# ESP32.net
KiCad netlist of a schematic drawn in Altium Designer
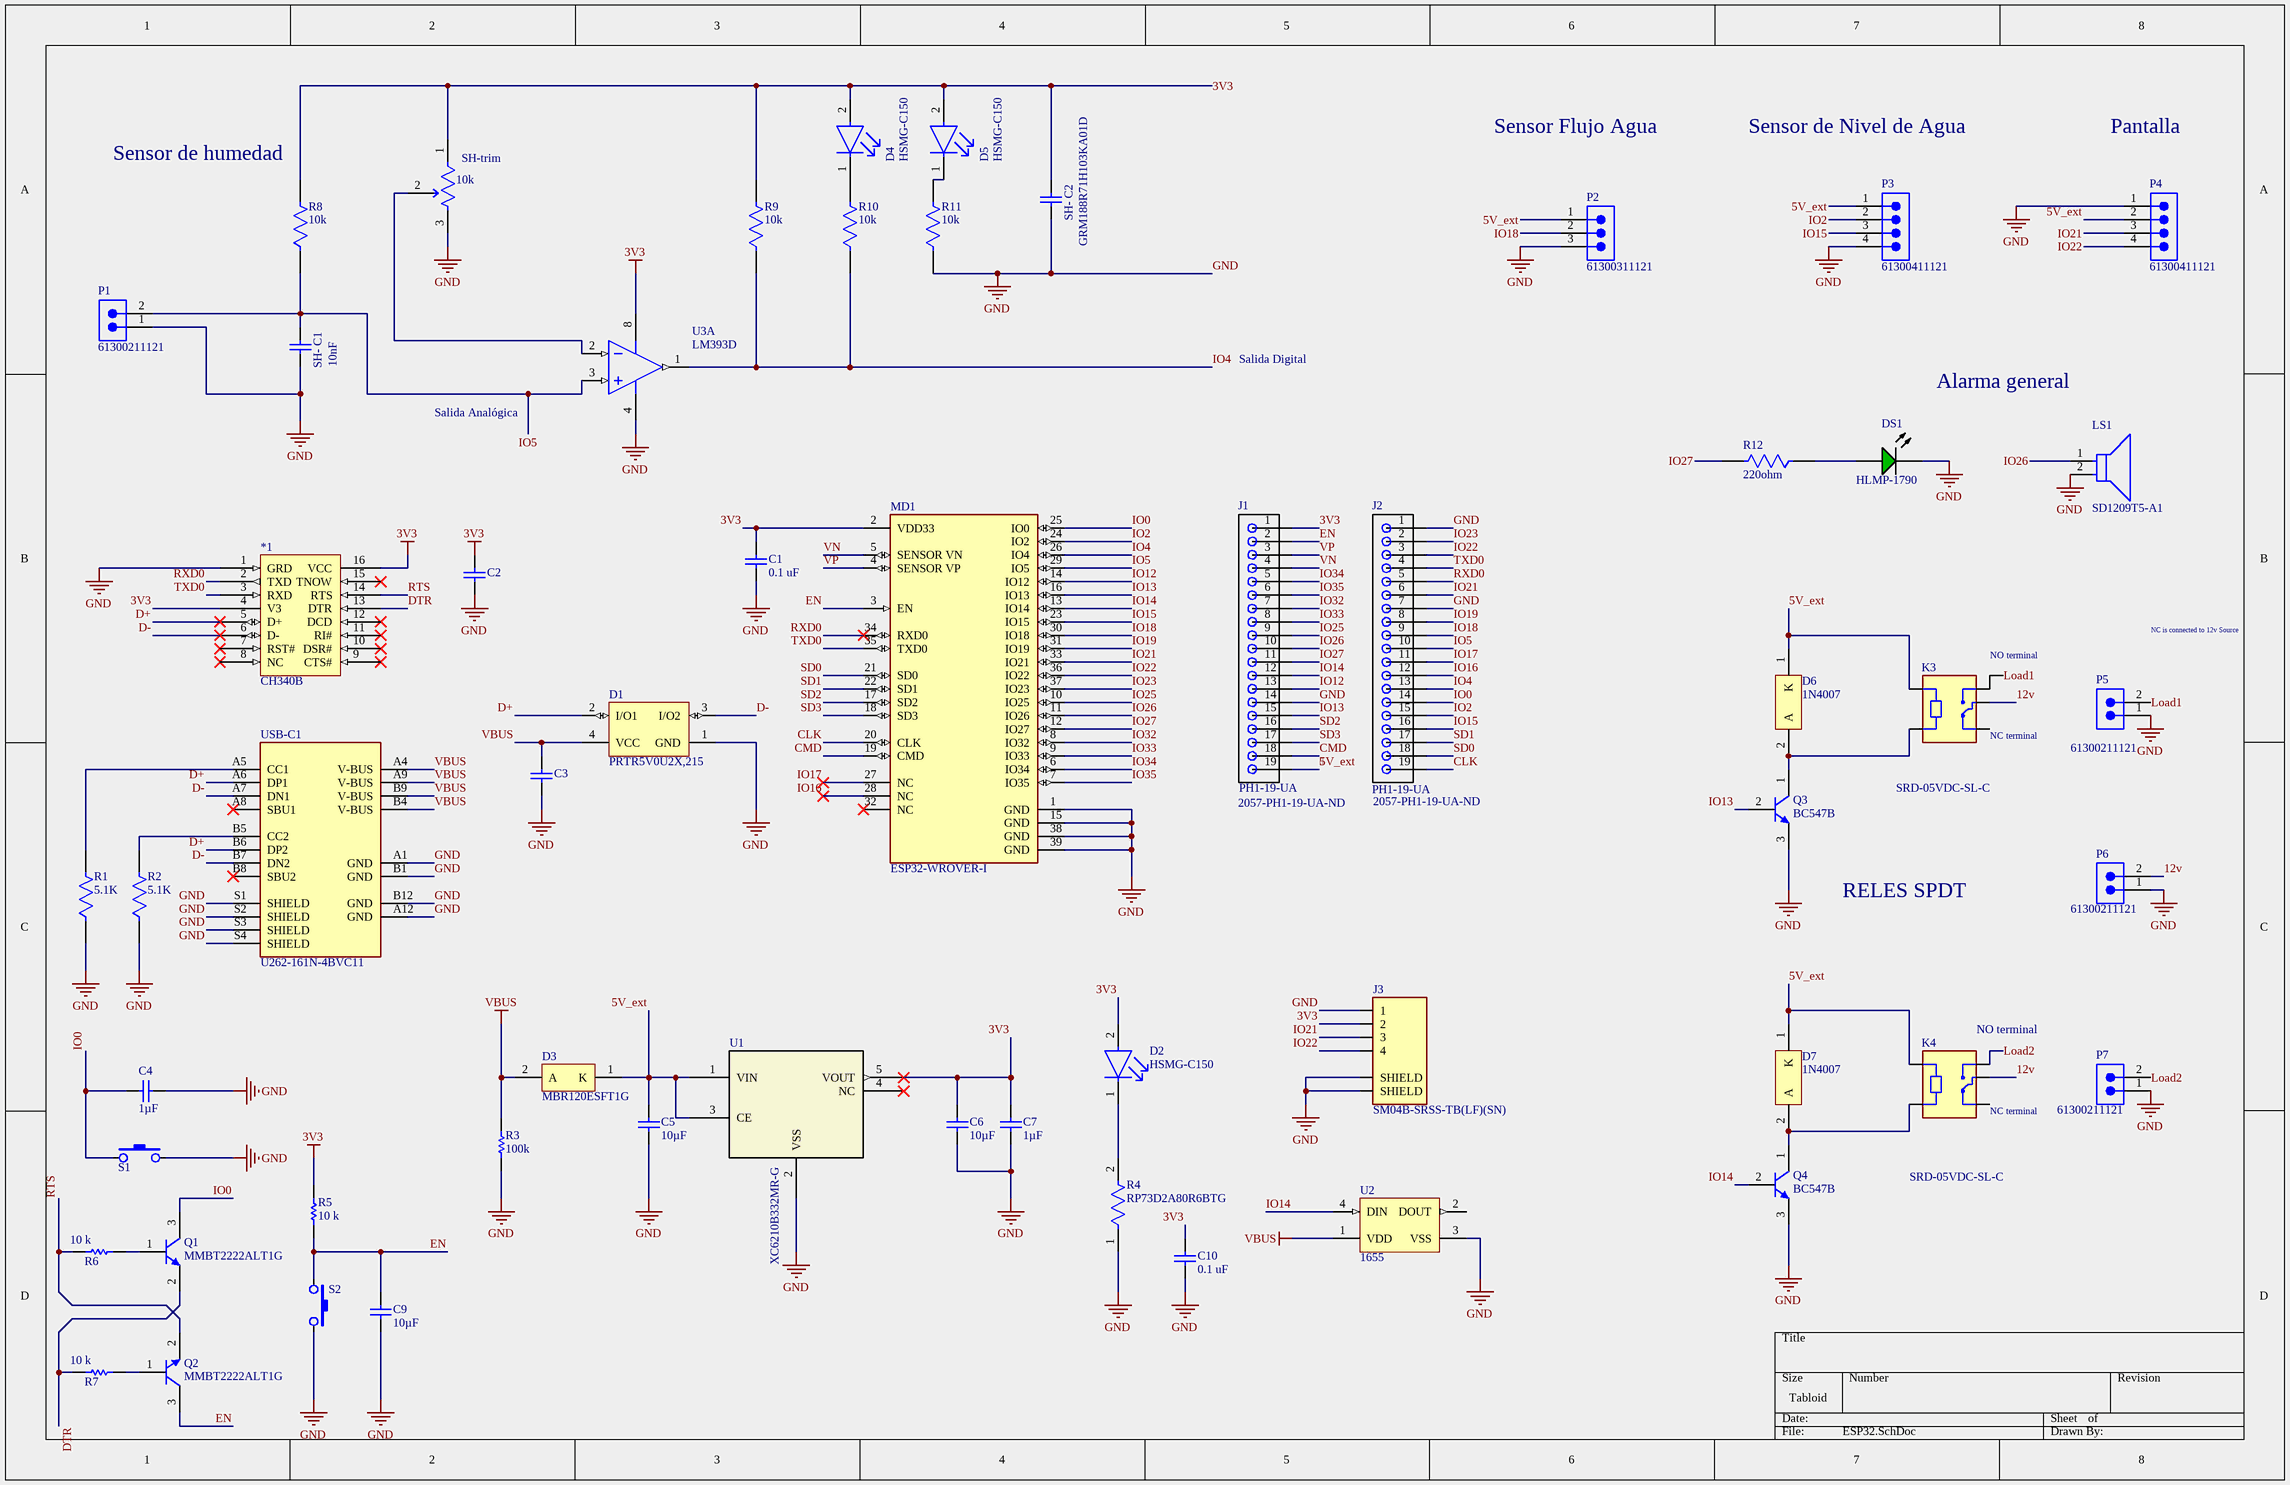
[diagram p0: ESP32.SchDoc]

(export (version "E")
  (design (tool "Eeschema 10.0.6"))
  (components
    (comp (ref "*1")
      (value "CH340B")
      (footprint "CH340B")
      (description "- USB 2.0 Transceiver 2Mbps SOP-16_150mil USB ICs ROHS")
      (libsource (lib "Isidro_Library") (part "CH340B"))
    )
    (comp (ref "C1")
      (value "0.1 uF")
      (footprint "CAPC2013X94X50ML20T25")
      (description "Chip Capacitor, Ceramic, 0.1 uF, 10%, 50 V, 0805, RoHS, Tape and Reel")
      (fields (field (name "MANUFACTURER") "AVX"))
      (libsource (lib "Altium Content Vault") (part "CAP-NP-2"))
    )
    (comp (ref "C2")
      (value "08055C104KAT2A")
      (footprint "CAPC2013X94X50ML20T25")
      (description "Chip Capacitor, Ceramic, 0.1 uF, 10%, 50 V, 0805, RoHS, Tape and Reel")
      (fields (field (name "MANUFACTURER") "AVX"))
      (libsource (lib "Altium Content Vault") (part "CAP-NP-2"))
    )
    (comp (ref "C3")
      (value "08055C104KAT2A")
      (footprint "CAPC2013X94X50ML20T25")
      (description "Chip Capacitor, Ceramic, 0.1 uF, 10%, 50 V, 0805, RoHS, Tape and Reel")
      (fields (field (name "MANUFACTURER") "AVX"))
      (libsource (lib "Altium Content Vault") (part "CAP-NP-2"))
    )
    (comp (ref "C4")
      (value "1µF")
      (footprint "CAPC2013X145X50ML20T25")
      (description "1µF ±10% 16V Ceramic Capacitor X7R 0805 (2012 Metric)")
      (fields (field (name "MANUFACTURER") "Kemet") (field (name "PART NUMBER") "C0805C105K4RAC7800"))
      (libsource (lib "Altium Content Vault") (part "CAP"))
    )
    (comp (ref "C5")
      (value "10µF")
      (footprint "CAPC2013X140X50ML20T25")
      (description "10µF ±10% 16V Ceramic Capacitor X5R 0805 (2012 Metric)")
      (fields (field (name "PART NUMBER") "CL21A106KOQNNNG"))
      (libsource (lib "Altium Content Vault") (part "CAP"))
    )
    (comp (ref "C6")
      (value "10µF")
      (footprint "CAPC2013X140X50ML20T25")
      (description "10µF ±10% 16V Ceramic Capacitor X5R 0805 (2012 Metric)")
      (fields (field (name "PART NUMBER") "CL21A106KOQNNNG"))
      (libsource (lib "Altium Content Vault") (part "CAP"))
    )
    (comp (ref "C7")
      (value "1µF")
      (footprint "CAPC2013X145X50ML20T25")
      (description "1µF ±10% 16V Ceramic Capacitor X7R 0805 (2012 Metric)")
      (fields (field (name "MANUFACTURER") "Kemet") (field (name "PART NUMBER") "C0805C105K4RAC7800"))
      (libsource (lib "Altium Content Vault") (part "CAP"))
    )
    (comp (ref "C9")
      (value "10µF")
      (footprint "CAPC2013X145X50ML20T25")
      (description "1µF ±10% 16V Ceramic Capacitor X7R 0805 (2012 Metric)")
      (fields (field (name "MANUFACTURER") "Kemet") (field (name "PART NUMBER") "C0805C105K4RAC7800"))
      (libsource (lib "Altium Content Vault") (part "CAP"))
    )
    (comp (ref "C10")
      (value "0.1 uF")
      (footprint "CAPC2013X94X50ML20T25")
      (description "Chip Capacitor, Ceramic, 0.1 uF, 10%, 50 V, 0805, RoHS, Tape and Reel")
      (fields (field (name "MANUFACTURER") "AVX"))
      (libsource (lib "Altium Content Vault") (part "CAP-NP-2"))
    )
    (comp (ref "D1")
      (value "PRTR5V0U2X,215")
      (footprint "NXP-SOT143B-4_V")
      (fields (field (name "MANUFACTURER") "NXP Semiconductors"))
      (libsource (lib "Altium Content Vault") (part "NXP-PRTR5V0U2X,215-4"))
    )
    (comp (ref "D2")
      (value "HSMG-C150")
      (footprint "FP-HSMG-C150-MFG")
      (description "LED GREEN DIFFUSED 1206 SMD")
      (fields
        (field (name "MANUFACTURER") "Broadcom")
        (field (name "OCTOPART") "https://octopart.com/hsmg-c150-broadcom-71131304")
      )
      (libsource (lib "Altium Content Vault") (part "8706943c75ba83719d021d2fdc84c58"))
    )
    (comp (ref "D3")
      (value "MBR120ESFT1G")
      (footprint "ONSC-SOD-123FL-2-498_V")
      (description "Schottky Power Rectifier, 2-Pin SOD-123, Pb-Free, Tape and Reel")
      (fields (field (name "MANUFACTURER") "On Semiconductor"))
      (libsource (lib "Altium Content Vault") (part "ONSC-D-K1A2-2_A"))
    )
    (comp (ref "D4")
      (value "HSMG-C150")
      (footprint "FP-HSMG-C150-MFG")
      (description "LED GREEN DIFFUSED 1206 SMD")
      (fields
        (field (name "MANUFACTURER") "Broadcom")
        (field (name "OCTOPART") "https://octopart.com/hsmg-c150-broadcom-71131304")
      )
      (libsource (lib "Altium Content Vault") (part "8706943c75ba83719d021d2fdc84c58"))
    )
    (comp (ref "D5")
      (value "HSMG-C150")
      (footprint "FP-HSMG-C150-MFG")
      (description "LED GREEN DIFFUSED 1206 SMD")
      (fields
        (field (name "MANUFACTURER") "Broadcom")
        (field (name "OCTOPART") "https://octopart.com/hsmg-c150-broadcom-71131304")
      )
      (libsource (lib "Altium Content Vault") (part "8706943c75ba83719d021d2fdc84c58"))
    )
    (comp (ref "D6")
      (value "1N4007")
      (footprint "ONSC-AXIAL_LEAD-2-59-10_P")
      (description "Standard Recovery Rectifier, 2-Pin Axial_Lead, Pb-Free, Bulk Bag")
      (fields (field (name "MANUFACTURER") "On Semiconductor"))
      (libsource (lib "") (part "ONSC-D-K1A2-2_A_1"))
    )
    (comp (ref "D7")
      (value "1N4007")
      (footprint "ONSC-AXIAL_LEAD-2-59-10_P")
      (description "Standard Recovery Rectifier, 2-Pin Axial_Lead, Pb-Free, Bulk Bag")
      (fields (field (name "MANUFACTURER") "On Semiconductor"))
      (libsource (lib "") (part "ONSC-D-K1A2-2_A_1"))
    )
    (comp (ref "DS1")
      (value "HLMP-1790")
      (footprint "LED-2P-2.54-3MM_V")
      (description "LED, Green, 2 mA, 1.9 V, -20 to 100 degC, 2-Pin THD, RoHS, Bulk")
      (fields (field (name "MANUFACTURER") "Avago"))
      (libsource (lib "Altium Content Vault") (part "LED_GREEN_A1K2-2"))
    )
    (comp (ref "J1")
      (value "PH1-19-UA")
      (footprint "PH1-19-UA")
      (description "Connector Header Through Hole 19 position 0.100\" (2.54mm)")
      (fields (field (name "SUPPLIER PART NUMBER 1") "2057-PH1-19-UA-ND"))
      (libsource (lib "Isidro_Library") (part "PH1-19-UA"))
    )
    (comp (ref "J2")
      (value "PH1-19-UA")
      (footprint "PH1-19-UA")
      (description "Connector Header Through Hole 19 position 0.100\" (2.54mm)")
      (fields (field (name "SUPPLIER PART NUMBER 1") "2057-PH1-19-UA-ND"))
      (libsource (lib "Isidro_Library") (part "PH1-19-UA"))
    )
    (comp (ref "J3")
      (value "SM04B-SRSS-TB(LF)(SN)")
      (footprint "JST_SM04B-SRSS-TB(LF)(SN)")
      (description "Connector Header Surface Mount, Right Angle 4 position 0.039 _1.00mm_")
      (fields (field (name "MF") "JST Sales") (field (name "MP") "SM04B-SRSS-TB_LF__SN_"))
      (libsource (lib "Isidro_Library") (part "SM04B-SRSS-TB(LF)(SN)"))
    )
    (comp (ref "K3")
      (value "SRD-05VDC-SL-C")
      (footprint "RELAY_SRD-05VDC-SL-C")
      (fields (field (name "MF") "Songle Relay"))
      (libsource (lib "SRD-05VDC-SL-C") (part "SRD-05VDC-SL-C"))
    )
    (comp (ref "K4")
      (value "SRD-05VDC-SL-C")
      (footprint "RELAY_SRD-05VDC-SL-C")
      (fields (field (name "MF") "Songle Relay"))
      (libsource (lib "SRD-05VDC-SL-C") (part "SRD-05VDC-SL-C"))
    )
    (comp (ref "LS1")
      (value "SD1209T5-A1")
      (footprint "FP-SD1209-MFG")
      (description "AUDIO MAGNETIC XDCR 3-6V TH")
      (libsource (lib "Altium Content Vault") (part "1973c4b650225fd2ddacaff6b763965"))
    )
    (comp (ref "MD1")
      (value "ESP32-WROVER-I")
      (footprint "FP-ESP32-WROVER-I-MFG")
      (description "SMD MODULE, ESP32-D0WDQ6, 32MBIT")
      (fields
        (field (name "MANUFACTURER") "Espressif")
        (field (name "OCTOPART") "https://octopart.com/esp32-wrover-i-espressif+systems-89171349")
      )
      (libsource (lib "Altium Content Vault") (part "cbbb37af8bcfe61dfd46ac9418f0340"))
    )
    (comp (ref "P1")
      (value "61300211121")
      (footprint "61300211121")
      (libsource (lib "Altium Content Vault") (part "Header_Male_1R_02P"))
    )
    (comp (ref "P2")
      (value "61300311121")
      (footprint "61300311121")
      (libsource (lib "Altium Content Vault") (part "Header_Male_1R_03P"))
    )
    (comp (ref "P3")
      (value "61300411121")
      (footprint "61300411121")
      (libsource (lib "Altium Content Vault") (part "Header_Male_1R_04P"))
    )
    (comp (ref "P4")
      (value "61300411121")
      (footprint "61300411121")
      (libsource (lib "Altium Content Vault") (part "Header_Male_1R_04P"))
    )
    (comp (ref "P5")
      (value "61300211121")
      (footprint "61300211121")
      (libsource (lib "Altium Content Vault") (part "Header_Male_1R_02P"))
    )
    (comp (ref "P6")
      (value "61300211121")
      (footprint "61300211121")
      (libsource (lib "Altium Content Vault") (part "Header_Male_1R_02P"))
    )
    (comp (ref "P7")
      (value "61300211121")
      (footprint "61300211121")
      (libsource (lib "Altium Content Vault") (part "Header_Male_1R_02P"))
    )
    (comp (ref "Q1")
      (value "MMBT2222ALT1G")
      (footprint "ONSC-SOT-23-3-318-08_V")
      (description "General Purpose Transistor, NPN Silicon, 3-Pin SOT-23, Pb-Free, Tape and Reel")
      (fields (field (name "MANUFACTURER") "On Semiconductor"))
      (libsource (lib "Altium Content Vault") (part "ONSC-NPN-B1E2C3-3"))
    )
    (comp (ref "Q2")
      (value "MMBT2222ALT1G")
      (footprint "ONSC-SOT-23-3-318-08_V")
      (description "General Purpose Transistor, NPN Silicon, 3-Pin SOT-23, Pb-Free, Tape and Reel")
      (fields (field (name "MANUFACTURER") "On Semiconductor"))
      (libsource (lib "Altium Content Vault") (part "ONSC-NPN-B1E2C3-3"))
    )
    (comp (ref "Q3")
      (value "BC547B")
      (footprint "ONSC-TO-92-3-29-11")
      (description "Amplifier Transistor, NPN Silicon, 3-Pin TO-92, Bulk Box")
      (fields (field (name "MANUFACTURER") "On Semiconductor"))
      (libsource (lib "Altium Content Vault") (part "ONSC-NPN-C1B2E3-3"))
    )
    (comp (ref "Q4")
      (value "BC547B")
      (footprint "ONSC-TO-92-3-29-11")
      (description "Amplifier Transistor, NPN Silicon, 3-Pin TO-92, Bulk Box")
      (fields (field (name "MANUFACTURER") "On Semiconductor"))
      (libsource (lib "Altium Content Vault") (part "ONSC-NPN-C1B2E3-3"))
    )
    (comp (ref "R1")
      (value "5.1K")
      (footprint "FP-CRCW0805-e3-MFG")
      (description "RES Thick Film, 5.1kΩ, 1%, 0.125W, 100ppm/°C, 0805")
      (fields (field (name "TOLERANCE") "1%"))
      (libsource (lib "Altium Content Vault") (part "1029c3af85768c4190bb7ad29bc67b5"))
    )
    (comp (ref "R2")
      (value "5.1K")
      (footprint "FP-CRCW0805-e3-MFG")
      (description "RES Thick Film, 5.1kΩ, 1%, 0.125W, 100ppm/°C, 0805")
      (fields (field (name "TOLERANCE") "1%"))
      (libsource (lib "Altium Content Vault") (part "1029c3af85768c4190bb7ad29bc67b5"))
    )
    (comp (ref "R3")
      (value "100k")
      (footprint "RESC2013X60X40ML20T25")
      (description "100 kOhms ±0.1% 0.125W, 1/8W Chip Resistor 0805 (2012 Metric) Automotive AEC-Q200 Thin Film")
      (fields (field (name "PART NUMBER") "ERA6AEB104V") (field (name "MANUFACTURER") "Panasonic"))
      (libsource (lib "Altium Content Vault") (part "RES"))
    )
    (comp (ref "R4")
      (value "RP73D2A80R6BTG")
      (footprint "FP-RP732A-MFG")
      (description "RESISTOR, 0805 80.6Ω, 0.1% 15ppm/°C")
      (fields
        (field (name "OCTOPART") "https://octopart.com/rp73d2a80r6btg-te+connectivity-42011633")
        (field (name "MANUFACTURER") "TE Connectivity")
      )
      (libsource (lib "") (part "1029c3af85768c4190bb7ad29bc67b5_1"))
    )
    (comp (ref "R5")
      (value "10 k")
      (footprint "RESC2013X60X30ML20T20")
      (fields (field (name "PART NUMBER") "RK73B2ATTD103J") (field (name "MANUFACTURER") "KOA Speer"))
      (libsource (lib "Altium Content Vault") (part "RES"))
    )
    (comp (ref "R6")
      (value "10 k")
      (footprint "RESC2013X60X30ML20T20")
      (fields (field (name "PART NUMBER") "RK73B2ATTD103J") (field (name "MANUFACTURER") "KOA Speer"))
      (libsource (lib "Altium Content Vault") (part "RES"))
    )
    (comp (ref "R7")
      (value "10 k")
      (footprint "RESC2013X60X30ML20T20")
      (fields (field (name "PART NUMBER") "RK73B2ATTD103J") (field (name "MANUFACTURER") "KOA Speer"))
      (libsource (lib "Altium Content Vault") (part "RES"))
    )
    (comp (ref "R8")
      (value "10k")
      (footprint "FP-CRCW0805-e3-MFG")
      (description "RES Thick Film, 5.1kΩ, 1%, 0.125W, 100ppm/°C, 0805")
      (fields (field (name "TOLERANCE") "1%"))
      (libsource (lib "Altium Content Vault") (part "1029c3af85768c4190bb7ad29bc67b5"))
    )
    (comp (ref "R9")
      (value "10k")
      (footprint "FP-CRCW0805-e3-MFG")
      (description "RES Thick Film, 5.1kΩ, 1%, 0.125W, 100ppm/°C, 0805")
      (fields (field (name "TOLERANCE") "1%"))
      (libsource (lib "Altium Content Vault") (part "1029c3af85768c4190bb7ad29bc67b5"))
    )
    (comp (ref "R10")
      (value "10k")
      (footprint "FP-CRCW0805-e3-MFG")
      (description "RES Thick Film, 5.1kΩ, 1%, 0.125W, 100ppm/°C, 0805")
      (fields (field (name "TOLERANCE") "1%"))
      (libsource (lib "Altium Content Vault") (part "1029c3af85768c4190bb7ad29bc67b5"))
    )
    (comp (ref "R11")
      (value "10k")
      (footprint "FP-CRCW0805-e3-MFG")
      (description "RES Thick Film, 5.1kΩ, 1%, 0.125W, 100ppm/°C, 0805")
      (fields (field (name "TOLERANCE") "1%"))
      (libsource (lib "Altium Content Vault") (part "1029c3af85768c4190bb7ad29bc67b5"))
    )
    (comp (ref "R12")
      (value "220ohm")
      (footprint "FP-CRCW0805-e3-MFG")
      (description "RES Thick Film, 5.1kΩ, 1%, 0.125W, 100ppm/°C, 0805")
      (fields (field (name "TOLERANCE") "1%"))
      (libsource (lib "Altium Content Vault") (part "1029c3af85768c4190bb7ad29bc67b5"))
    )
    (comp (ref "S1")
      (value "IO0")
      (footprint "SMT_SW_PTS_820")
      (libsource (lib "SnapEDAsch") (part "PTS820J25MSMTRLFS"))
    )
    (comp (ref "S2")
      (value "PTS820J25MSMTRLFS")
      (footprint "SMT_SW_PTS_820")
      (libsource (lib "SnapEDAsch") (part "PTS820J25MSMTRLFS"))
    )
    (comp (ref "SH- C1")
      (value "10nF")
      (footprint "CAPC1608X90X35ML10T15")
      (description "Chip Capacitor, 10 nF, +/- 10%, 50 V, -55 to 125 degC, 0603 (1608 Metric), RoHS, Tape and Reel")
      (fields (field (name "VOLTAGE") "50V") (field (name "TOLERANCE") "10%"))
      (libsource (lib "Altium Content Vault") (part "CAP-NP-2"))
    )
    (comp (ref "SH- C2")
      (value "GRM188R71H103KA01D")
      (footprint "CAPC1608X90X35ML10T15")
      (description "Chip Capacitor, 10 nF, +/- 10%, 50 V, -55 to 125 degC, 0603 (1608 Metric), RoHS, Tape and Reel")
      (fields (field (name "VOLTAGE") "50V") (field (name "TOLERANCE") "10%"))
      (libsource (lib "Altium Content Vault") (part "CAP-NP-2"))
    )
    (comp (ref "SH-trim")
      (value "10k")
      (footprint "FP-3362P-1-102TLF-MFG")
      (description "10k POT")
      (fields (field (name "TOLERANCE") "10%"))
      (libsource (lib "Altium Content Vault") (part "2dcfd2547301a7d3209a5e99acfd772"))
    )
    (comp (ref "U1")
      (value "XC6210B332MR-G")
      (footprint "SOT-25_TOR-M")
      (description "No Description Available")
      (fields (field (name "COPYRIGHT") "Copyright (C) 2022 Ultra Librarian. All rights reserved."))
      (libsource (lib "Isidro_Library") (part "XC6210B332MR-G"))
    )
    (comp (ref "U2")
      (value "1655")
      (footprint "ADA-RGB-1655_V")
      (fields (field (name "MANUFACTURER") "Adafruit-Industries-LLC"))
      (libsource (lib "Altium Content Vault") (part "ADA-RGB-1655-4"))
    )
    (comp (ref "U3")
      (value "LM393D")
      (footprint "D0008A_M")
      (description "Dual Differential Comparator, 2 to 30 V, 0 to 70 degC, 8-pin SOIC (D8), Green (RoHS & no Sb/Br)")
      (fields (field (name "MANUFACTURER") "TexasInstruments"))
      (libsource (lib "Altium Content Vault") (part "TI-LM393-D8"))
    )
    (comp (ref "USB-C1")
      (value "U262-161N-4BVC11")
      (footprint "U262-161N-4BVC11")
      (description "USB - Type C Female 16 SMT USB Connectors RoHS")
      (libsource (lib "AQIMon") (part "U262-161N-4BVC11"))
    )
  )
  (nets
    (net (code "1") (name "/") (class "Default")
      (node (ref "C5") (pin "2") (pinfunction "2_2") (pintype "passive"))
      (node (ref "D3") (pin "1") (pinfunction "K_1") (pintype "passive"))
      (node (ref "D6") (pin "1") (pinfunction "K_1") (pintype "passive"))
      (node (ref "D7") (pin "1") (pinfunction "K_1") (pintype "passive"))
      (node (ref "J1") (pin "19") (pinfunction "19_19") (pintype "passive"))
      (node (ref "K3") (pin "A1") (pinfunction "A1_A1") (pintype "passive"))
      (node (ref "K4") (pin "A1") (pinfunction "A1_A1") (pintype "passive"))
      (node (ref "P2") (pin "1") (pinfunction "1_1") (pintype "passive"))
      (node (ref "P3") (pin "1") (pinfunction "1_1") (pintype "passive"))
      (node (ref "P4") (pin "2") (pinfunction "2_2") (pintype "passive"))
      (node (ref "U1") (pin "1") (pinfunction "VIN_1") (pintype "power_in"))
      (node (ref "U1") (pin "3") (pinfunction "CE_3") (pintype "passive"))
    )
    (net (code "2") (name "/12v") (class "Default")
      (node (ref "K3") (pin "COM") (pinfunction "COM_COM") (pintype "passive"))
      (node (ref "K4") (pin "COM") (pinfunction "COM_COM") (pintype "passive"))
      (node (ref "P6") (pin "2") (pinfunction "2_2") (pintype "passive"))
    )
    (net (code "3") (name "/CLK") (class "Default")
      (node (ref "J2") (pin "19") (pinfunction "19_19") (pintype "passive"))
      (node (ref "MD1") (pin "20") (pinfunction "CLK_20") (pintype "bidirectional"))
    )
    (net (code "4") (name "/CMD") (class "Default")
      (node (ref "J1") (pin "18") (pinfunction "18_18") (pintype "passive"))
      (node (ref "MD1") (pin "19") (pinfunction "CMD_19") (pintype "bidirectional"))
    )
    (net (code "5") (name "/D+") (class "Default")
      (node (ref "*1") (pin "5") (pinfunction "D+_5") (pintype "bidirectional"))
      (node (ref "D1") (pin "2") (pinfunction "I/O1_2") (pintype "bidirectional"))
      (node (ref "USB-C1") (pin "A6") (pinfunction "DP1_A6") (pintype "power_in"))
      (node (ref "USB-C1") (pin "B6") (pinfunction "DP2_B6") (pintype "power_in"))
    )
    (net (code "6") (name "/D-") (class "Default")
      (node (ref "*1") (pin "6") (pinfunction "D-_6") (pintype "bidirectional"))
      (node (ref "D1") (pin "3") (pinfunction "I/O2_3") (pintype "bidirectional"))
      (node (ref "USB-C1") (pin "A7") (pinfunction "DN1_A7") (pintype "power_in"))
      (node (ref "USB-C1") (pin "B7") (pinfunction "DN2_B7") (pintype "power_in"))
    )
    (net (code "7") (name "/DTR") (class "Default")
      (node (ref "*1") (pin "13") (pinfunction "DTR_13") (pintype "input"))
      (node (ref "Q1") (pin "2") (pinfunction "E_2") (pintype "passive"))
      (node (ref "R7") (pin "2") (pinfunction "2_2") (pintype "passive"))
    )
    (net (code "8") (name "/EN") (class "Default")
      (node (ref "C9") (pin "2") (pinfunction "2_2") (pintype "passive"))
      (node (ref "J1") (pin "2") (pinfunction "2_2") (pintype "passive"))
      (node (ref "MD1") (pin "3") (pinfunction "EN_3") (pintype "input"))
      (node (ref "Q2") (pin "3") (pinfunction "C_3") (pintype "passive"))
      (node (ref "R5") (pin "1") (pinfunction "1_1") (pintype "passive"))
      (node (ref "S2") (pin "1") (pinfunction "1_1") (pintype "passive"))
    )
    (net (code "9") (name "/IO0") (class "Default")
      (node (ref "C4") (pin "2") (pinfunction "2_2") (pintype "passive"))
      (node (ref "J2") (pin "14") (pinfunction "14_14") (pintype "passive"))
      (node (ref "MD1") (pin "25") (pinfunction "IO0_25") (pintype "bidirectional"))
      (node (ref "Q1") (pin "3") (pinfunction "C_3") (pintype "passive"))
      (node (ref "S1") (pin "1") (pinfunction "1_1") (pintype "passive"))
    )
    (net (code "10") (name "/IO2") (class "Default")
      (node (ref "J2") (pin "15") (pinfunction "15_15") (pintype "passive"))
      (node (ref "MD1") (pin "24") (pinfunction "IO2_24") (pintype "bidirectional"))
      (node (ref "P3") (pin "2") (pinfunction "2_2") (pintype "passive"))
    )
    (net (code "11") (name "/IO4") (class "Default")
      (node (ref "J2") (pin "13") (pinfunction "13_13") (pintype "passive"))
      (node (ref "MD1") (pin "26") (pinfunction "IO4_26") (pintype "bidirectional"))
      (node (ref "R10") (pin "1") (pinfunction "1_1") (pintype "passive"))
      (node (ref "R9") (pin "1") (pinfunction "1_1") (pintype "passive"))
      (node (ref "U3") (pin "1") (pinfunction "1OUT_1") (pintype "output"))
    )
    (net (code "12") (name "/IO5") (class "Default")
      (node (ref "J2") (pin "10") (pinfunction "10_10") (pintype "passive"))
      (node (ref "MD1") (pin "29") (pinfunction "IO5_29") (pintype "bidirectional"))
      (node (ref "P1") (pin "2") (pinfunction "2_2") (pintype "passive"))
      (node (ref "R8") (pin "1") (pinfunction "1_1") (pintype "passive"))
      (node (ref "SH- C1") (pin "2") (pinfunction "2_2") (pintype "passive"))
      (node (ref "U3") (pin "3") (pinfunction "1IN+_3") (pintype "input"))
    )
    (net (code "13") (name "/IO12") (class "Default")
      (node (ref "J1") (pin "13") (pinfunction "13_13") (pintype "passive"))
      (node (ref "MD1") (pin "14") (pinfunction "IO12_14") (pintype "bidirectional"))
    )
    (net (code "14") (name "/IO13") (class "Default")
      (node (ref "J1") (pin "15") (pinfunction "15_15") (pintype "passive"))
      (node (ref "MD1") (pin "16") (pinfunction "IO13_16") (pintype "bidirectional"))
      (node (ref "Q3") (pin "2") (pinfunction "B_2") (pintype "passive"))
    )
    (net (code "15") (name "/IO14") (class "Default")
      (node (ref "J1") (pin "12") (pinfunction "12_12") (pintype "passive"))
      (node (ref "MD1") (pin "13") (pinfunction "IO14_13") (pintype "bidirectional"))
      (node (ref "Q4") (pin "2") (pinfunction "B_2") (pintype "passive"))
      (node (ref "U2") (pin "4") (pinfunction "DIN_4") (pintype "input"))
    )
    (net (code "16") (name "/IO15") (class "Default")
      (node (ref "J2") (pin "16") (pinfunction "16_16") (pintype "passive"))
      (node (ref "MD1") (pin "23") (pinfunction "IO15_23") (pintype "bidirectional"))
      (node (ref "P3") (pin "3") (pinfunction "3_3") (pintype "passive"))
    )
    (net (code "17") (name "/IO16") (class "Default")
      (node (ref "J2") (pin "12") (pinfunction "12_12") (pintype "passive"))
      (node (ref "MD1") (pin "28") (pinfunction "NC_28") (pintype "passive"))
    )
    (net (code "18") (name "/IO17") (class "Default")
      (node (ref "J2") (pin "11") (pinfunction "11_11") (pintype "passive"))
      (node (ref "MD1") (pin "27") (pinfunction "NC_27") (pintype "passive"))
    )
    (net (code "19") (name "/IO18") (class "Default")
      (node (ref "J2") (pin "9") (pinfunction "9_9") (pintype "passive"))
      (node (ref "MD1") (pin "30") (pinfunction "IO18_30") (pintype "bidirectional"))
      (node (ref "P2") (pin "2") (pinfunction "2_2") (pintype "passive"))
    )
    (net (code "20") (name "/IO19") (class "Default")
      (node (ref "J2") (pin "8") (pinfunction "8_8") (pintype "passive"))
      (node (ref "MD1") (pin "31") (pinfunction "IO19_31") (pintype "bidirectional"))
    )
    (net (code "21") (name "/IO21") (class "Default")
      (node (ref "J2") (pin "6") (pinfunction "6_6") (pintype "passive"))
      (node (ref "J3") (pin "3") (pinfunction "3_3") (pintype "passive"))
      (node (ref "MD1") (pin "33") (pinfunction "IO21_33") (pintype "bidirectional"))
      (node (ref "P4") (pin "3") (pinfunction "3_3") (pintype "passive"))
    )
    (net (code "22") (name "/IO22") (class "Default")
      (node (ref "J2") (pin "3") (pinfunction "3_3") (pintype "passive"))
      (node (ref "J3") (pin "4") (pinfunction "4_4") (pintype "passive"))
      (node (ref "MD1") (pin "36") (pinfunction "IO22_36") (pintype "bidirectional"))
      (node (ref "P4") (pin "4") (pinfunction "4_4") (pintype "passive"))
    )
    (net (code "23") (name "/IO23") (class "Default")
      (node (ref "J2") (pin "2") (pinfunction "2_2") (pintype "passive"))
      (node (ref "MD1") (pin "37") (pinfunction "IO23_37") (pintype "bidirectional"))
    )
    (net (code "24") (name "/IO25") (class "Default")
      (node (ref "J1") (pin "9") (pinfunction "9_9") (pintype "passive"))
      (node (ref "MD1") (pin "10") (pinfunction "IO25_10") (pintype "bidirectional"))
    )
    (net (code "25") (name "/IO26") (class "Default")
      (node (ref "J1") (pin "10") (pinfunction "10_10") (pintype "passive"))
      (node (ref "LS1") (pin "1") (pinfunction "C_1") (pintype "passive"))
      (node (ref "MD1") (pin "11") (pinfunction "IO26_11") (pintype "bidirectional"))
    )
    (net (code "26") (name "/IO27") (class "Default")
      (node (ref "J1") (pin "11") (pinfunction "11_11") (pintype "passive"))
      (node (ref "MD1") (pin "12") (pinfunction "IO27_12") (pintype "bidirectional"))
      (node (ref "R12") (pin "2") (pinfunction "2_2") (pintype "passive"))
    )
    (net (code "27") (name "/IO32") (class "Default")
      (node (ref "J1") (pin "7") (pinfunction "7_7") (pintype "passive"))
      (node (ref "MD1") (pin "8") (pinfunction "IO32_8") (pintype "bidirectional"))
    )
    (net (code "28") (name "/IO33") (class "Default")
      (node (ref "J1") (pin "8") (pinfunction "8_8") (pintype "passive"))
      (node (ref "MD1") (pin "9") (pinfunction "IO33_9") (pintype "bidirectional"))
    )
    (net (code "29") (name "/IO34") (class "Default")
      (node (ref "J1") (pin "5") (pinfunction "5_5") (pintype "passive"))
      (node (ref "MD1") (pin "6") (pinfunction "IO34_6") (pintype "bidirectional"))
    )
    (net (code "30") (name "/IO35") (class "Default")
      (node (ref "J1") (pin "6") (pinfunction "6_6") (pintype "passive"))
      (node (ref "MD1") (pin "7") (pinfunction "IO35_7") (pintype "bidirectional"))
    )
    (net (code "31") (name "/Load1") (class "Default")
      (node (ref "K3") (pin "NO") (pinfunction "NO_NO") (pintype "passive"))
      (node (ref "P5") (pin "2") (pinfunction "2_2") (pintype "passive"))
    )
    (net (code "32") (name "/Load2") (class "Default")
      (node (ref "K4") (pin "NO") (pinfunction "NO_NO") (pintype "passive"))
      (node (ref "P7") (pin "2") (pinfunction "2_2") (pintype "passive"))
    )
    (net (code "33") (name "/RTS") (class "Default")
      (node (ref "*1") (pin "14") (pinfunction "RTS_14") (pintype "input"))
      (node (ref "Q2") (pin "2") (pinfunction "E_2") (pintype "passive"))
      (node (ref "R6") (pin "2") (pinfunction "2_2") (pintype "passive"))
    )
    (net (code "34") (name "/RXD0") (class "Default")
      (node (ref "*1") (pin "2") (pinfunction "TXD_2") (pintype "output"))
      (node (ref "J2") (pin "5") (pinfunction "5_5") (pintype "passive"))
      (node (ref "MD1") (pin "34") (pinfunction "RXD0_34") (pintype "bidirectional"))
    )
    (net (code "35") (name "/SD0") (class "Default")
      (node (ref "J2") (pin "18") (pinfunction "18_18") (pintype "passive"))
      (node (ref "MD1") (pin "21") (pinfunction "SD0_21") (pintype "bidirectional"))
    )
    (net (code "36") (name "/SD1") (class "Default")
      (node (ref "J2") (pin "17") (pinfunction "17_17") (pintype "passive"))
      (node (ref "MD1") (pin "22") (pinfunction "SD1_22") (pintype "bidirectional"))
    )
    (net (code "37") (name "/SD2") (class "Default")
      (node (ref "J1") (pin "16") (pinfunction "16_16") (pintype "passive"))
      (node (ref "MD1") (pin "17") (pinfunction "SD2_17") (pintype "bidirectional"))
    )
    (net (code "38") (name "/SD3") (class "Default")
      (node (ref "J1") (pin "17") (pinfunction "17_17") (pintype "passive"))
      (node (ref "MD1") (pin "18") (pinfunction "SD3_18") (pintype "bidirectional"))
    )
    (net (code "39") (name "/TXD0") (class "Default")
      (node (ref "*1") (pin "3") (pinfunction "RXD_3") (pintype "input"))
      (node (ref "J2") (pin "4") (pinfunction "4_4") (pintype "passive"))
      (node (ref "MD1") (pin "35") (pinfunction "TXD0_35") (pintype "bidirectional"))
    )
    (net (code "40") (name "/VN") (class "Default")
      (node (ref "J1") (pin "4") (pinfunction "4_4") (pintype "passive"))
      (node (ref "MD1") (pin "5") (pinfunction "SENSOR_VN_5") (pintype "bidirectional"))
    )
    (net (code "41") (name "/VP") (class "Default")
      (node (ref "J1") (pin "3") (pinfunction "3_3") (pintype "passive"))
      (node (ref "MD1") (pin "4") (pinfunction "SENSOR_VP_4") (pintype "bidirectional"))
    )
    (net (code "42") (name "3V3") (class "Default")
      (node (ref "*1") (pin "16") (pinfunction "VCC_16") (pintype "power_in"))
      (node (ref "*1") (pin "4") (pinfunction "V3_4") (pintype "power_in"))
      (node (ref "C1") (pin "2") (pinfunction "2_2") (pintype "passive"))
      (node (ref "C10") (pin "2") (pinfunction "2_2") (pintype "passive"))
      (node (ref "C2") (pin "2") (pinfunction "2_2") (pintype "passive"))
      (node (ref "C6") (pin "2") (pinfunction "2_2") (pintype "passive"))
      (node (ref "C7") (pin "2") (pinfunction "2_2") (pintype "passive"))
      (node (ref "D2") (pin "2") (pinfunction "A_2") (pintype "passive"))
      (node (ref "D4") (pin "2") (pinfunction "A_2") (pintype "passive"))
      (node (ref "D5") (pin "2") (pinfunction "A_2") (pintype "passive"))
      (node (ref "J1") (pin "1") (pinfunction "1_1") (pintype "passive"))
      (node (ref "J3") (pin "2") (pinfunction "2_2") (pintype "passive"))
      (node (ref "MD1") (pin "2") (pinfunction "VDD33_2") (pintype "power_in"))
      (node (ref "R5") (pin "2") (pinfunction "2_2") (pintype "passive"))
      (node (ref "R8") (pin "2") (pinfunction "2_2") (pintype "passive"))
      (node (ref "R9") (pin "2") (pinfunction "2_2") (pintype "passive"))
      (node (ref "SH- C2") (pin "2") (pinfunction "2_2") (pintype "passive"))
      (node (ref "SH-trim") (pin "1") (pinfunction "CCW_1") (pintype "passive"))
      (node (ref "U1") (pin "5") (pinfunction "VOUT_5") (pintype "output"))
      (node (ref "U3") (pin "8") (pinfunction "VCC_8") (pintype "power_in"))
    )
    (net (code "43") (name "GND") (class "Default")
      (node (ref "*1") (pin "1") (pinfunction "GRD_1") (pintype "input"))
      (node (ref "C1") (pin "1") (pinfunction "1_1") (pintype "passive"))
      (node (ref "C10") (pin "1") (pinfunction "1_1") (pintype "passive"))
      (node (ref "C2") (pin "1") (pinfunction "1_1") (pintype "passive"))
      (node (ref "C3") (pin "1") (pinfunction "1_1") (pintype "passive"))
      (node (ref "C4") (pin "1") (pinfunction "1_1") (pintype "passive"))
      (node (ref "C5") (pin "1") (pinfunction "1_1") (pintype "passive"))
      (node (ref "C6") (pin "1") (pinfunction "1_1") (pintype "passive"))
      (node (ref "C7") (pin "1") (pinfunction "1_1") (pintype "passive"))
      (node (ref "C9") (pin "1") (pinfunction "1_1") (pintype "passive"))
      (node (ref "D1") (pin "1") (pinfunction "GND_1") (pintype "power_in"))
      (node (ref "DS1") (pin "2") (pinfunction "K_2") (pintype "passive"))
      (node (ref "J1") (pin "14") (pinfunction "14_14") (pintype "passive"))
      (node (ref "J2") (pin "1") (pinfunction "1_1") (pintype "passive"))
      (node (ref "J2") (pin "7") (pinfunction "7_7") (pintype "passive"))
      (node (ref "J3") (pin "1") (pinfunction "1_1") (pintype "passive"))
      (node (ref "J3") (pin "S1") (pinfunction "SHIELD_S1") (pintype "passive"))
      (node (ref "J3") (pin "S2") (pinfunction "SHIELD_S2") (pintype "passive"))
      (node (ref "LS1") (pin "2") (pinfunction "A_2") (pintype "passive"))
      (node (ref "MD1") (pin "1") (pinfunction "GND_1") (pintype "power_in"))
      (node (ref "MD1") (pin "15") (pinfunction "GND_15") (pintype "power_in"))
      (node (ref "MD1") (pin "38") (pinfunction "GND_38") (pintype "power_in"))
      (node (ref "MD1") (pin "39") (pinfunction "GND_39") (pintype "power_in"))
      (node (ref "P1") (pin "1") (pinfunction "1_1") (pintype "passive"))
      (node (ref "P2") (pin "3") (pinfunction "3_3") (pintype "passive"))
      (node (ref "P3") (pin "4") (pinfunction "4_4") (pintype "passive"))
      (node (ref "P4") (pin "1") (pinfunction "1_1") (pintype "passive"))
      (node (ref "P5") (pin "1") (pinfunction "1_1") (pintype "passive"))
      (node (ref "P6") (pin "1") (pinfunction "1_1") (pintype "passive"))
      (node (ref "P7") (pin "1") (pinfunction "1_1") (pintype "passive"))
      (node (ref "Q3") (pin "3") (pinfunction "E_3") (pintype "passive"))
      (node (ref "Q4") (pin "3") (pinfunction "E_3") (pintype "passive"))
      (node (ref "R1") (pin "1") (pinfunction "1_1") (pintype "passive"))
      (node (ref "R11") (pin "1") (pinfunction "1_1") (pintype "passive"))
      (node (ref "R2") (pin "1") (pinfunction "1_1") (pintype "passive"))
      (node (ref "R3") (pin "1") (pinfunction "1_1") (pintype "passive"))
      (node (ref "R4") (pin "1") (pinfunction "1_1") (pintype "passive"))
      (node (ref "S1") (pin "2") (pinfunction "2_2") (pintype "passive"))
      (node (ref "S2") (pin "2") (pinfunction "2_2") (pintype "passive"))
      (node (ref "SH- C1") (pin "1") (pinfunction "1_1") (pintype "passive"))
      (node (ref "SH- C2") (pin "1") (pinfunction "1_1") (pintype "passive"))
      (node (ref "SH-trim") (pin "3") (pinfunction "CW_3") (pintype "passive"))
      (node (ref "U1") (pin "2") (pinfunction "VSS_2") (pintype "passive"))
      (node (ref "U2") (pin "3") (pinfunction "VSS_3") (pintype "power_in"))
      (node (ref "U3") (pin "4") (pinfunction "GND_4") (pintype "power_in"))
      (node (ref "USB-C1") (pin "A1") (pinfunction "GND_A1") (pintype "power_in"))
      (node (ref "USB-C1") (pin "A12") (pinfunction "GND_A12") (pintype "power_in"))
      (node (ref "USB-C1") (pin "B1") (pinfunction "GND_B1") (pintype "power_in"))
      (node (ref "USB-C1") (pin "B12") (pinfunction "GND_B12") (pintype "power_in"))
      (node (ref "USB-C1") (pin "S1") (pinfunction "SHIELD_S1") (pintype "passive"))
      (node (ref "USB-C1") (pin "S2") (pinfunction "SHIELD_S2") (pintype "passive"))
      (node (ref "USB-C1") (pin "S3") (pinfunction "SHIELD_S3") (pintype "passive"))
      (node (ref "USB-C1") (pin "S4") (pinfunction "SHIELD_S4") (pintype "passive"))
    )
    (net (code "44") (name "Net-(D2-C)") (class "Default")
      (node (ref "D2") (pin "1") (pinfunction "C_1") (pintype "passive"))
      (node (ref "R4") (pin "2") (pinfunction "2_2") (pintype "passive"))
    )
    (net (code "45") (name "Net-(D4-C)") (class "Default")
      (node (ref "D4") (pin "1") (pinfunction "C_1") (pintype "passive"))
      (node (ref "R10") (pin "2") (pinfunction "2_2") (pintype "passive"))
    )
    (net (code "46") (name "Net-(D5-C)") (class "Default")
      (node (ref "D5") (pin "1") (pinfunction "C_1") (pintype "passive"))
      (node (ref "R11") (pin "2") (pinfunction "2_2") (pintype "passive"))
    )
    (net (code "47") (name "Net-(D6-A)") (class "Default")
      (node (ref "D6") (pin "2") (pinfunction "A_2") (pintype "passive"))
      (node (ref "K3") (pin "A2") (pinfunction "A2_A2") (pintype "passive"))
      (node (ref "Q3") (pin "1") (pinfunction "C_1") (pintype "passive"))
    )
    (net (code "48") (name "Net-(D7-A)") (class "Default")
      (node (ref "D7") (pin "2") (pinfunction "A_2") (pintype "passive"))
      (node (ref "K4") (pin "A2") (pinfunction "A2_A2") (pintype "passive"))
      (node (ref "Q4") (pin "1") (pinfunction "C_1") (pintype "passive"))
    )
    (net (code "49") (name "Net-(DS1-A)") (class "Default")
      (node (ref "DS1") (pin "1") (pinfunction "A_1") (pintype "passive"))
      (node (ref "R12") (pin "1") (pinfunction "1_1") (pintype "passive"))
    )
    (net (code "50") (name "Net-(Q1-B)") (class "Default")
      (node (ref "Q1") (pin "1") (pinfunction "B_1") (pintype "passive"))
      (node (ref "R6") (pin "1") (pinfunction "1_1") (pintype "passive"))
    )
    (net (code "51") (name "Net-(Q2-B)") (class "Default")
      (node (ref "Q2") (pin "1") (pinfunction "B_1") (pintype "passive"))
      (node (ref "R7") (pin "1") (pinfunction "1_1") (pintype "passive"))
    )
    (net (code "52") (name "Net-(SH-trim-WIPER)") (class "Default")
      (node (ref "SH-trim") (pin "2") (pinfunction "WIPER_2") (pintype "passive"))
      (node (ref "U3") (pin "2") (pinfunction "1IN-_2") (pintype "input"))
    )
    (net (code "53") (name "Net-(USB-C1-CC1)") (class "Default")
      (node (ref "R1") (pin "2") (pinfunction "2_2") (pintype "passive"))
      (node (ref "USB-C1") (pin "A5") (pinfunction "CC1_A5") (pintype "power_in"))
    )
    (net (code "54") (name "Net-(USB-C1-CC2)") (class "Default")
      (node (ref "R2") (pin "2") (pinfunction "2_2") (pintype "passive"))
      (node (ref "USB-C1") (pin "B5") (pinfunction "CC2_B5") (pintype "power_in"))
    )
    (net (code "55") (name "VBUS") (class "Default")
      (node (ref "C3") (pin "2") (pinfunction "2_2") (pintype "passive"))
      (node (ref "D1") (pin "4") (pinfunction "VCC_4") (pintype "power_in"))
      (node (ref "D3") (pin "2") (pinfunction "A_2") (pintype "passive"))
      (node (ref "R3") (pin "2") (pinfunction "2_2") (pintype "passive"))
      (node (ref "U2") (pin "1") (pinfunction "VDD_1") (pintype "power_in"))
      (node (ref "USB-C1") (pin "A4") (pinfunction "V-BUS_A4") (pintype "power_in"))
      (node (ref "USB-C1") (pin "A9") (pinfunction "V-BUS_A9") (pintype "power_in"))
      (node (ref "USB-C1") (pin "B4") (pinfunction "V-BUS_B4") (pintype "power_in"))
      (node (ref "USB-C1") (pin "B9") (pinfunction "V-BUS_B9") (pintype "power_in"))
    )
    (net (code "56") (name "unconnected-(*1-CTS#-Pad9)") (class "Default")
      (node (ref "*1") (pin "9") (pinfunction "CTS#_9") (pintype "input+no_connect"))
    )
    (net (code "57") (name "unconnected-(*1-DCD-Pad12)") (class "Default")
      (node (ref "*1") (pin "12") (pinfunction "DCD_12") (pintype "input+no_connect"))
    )
    (net (code "58") (name "unconnected-(*1-DSR#-Pad10)") (class "Default")
      (node (ref "*1") (pin "10") (pinfunction "DSR#_10") (pintype "input+no_connect"))
    )
    (net (code "59") (name "unconnected-(*1-NC-Pad8)") (class "Default")
      (node (ref "*1") (pin "8") (pinfunction "NC_8") (pintype "input+no_connect"))
    )
    (net (code "60") (name "unconnected-(*1-RI#-Pad11)") (class "Default")
      (node (ref "*1") (pin "11") (pinfunction "RI#_11") (pintype "input+no_connect"))
    )
    (net (code "61") (name "unconnected-(*1-RST#-Pad7)") (class "Default")
      (node (ref "*1") (pin "7") (pinfunction "RST#_7") (pintype "input+no_connect"))
    )
    (net (code "62") (name "unconnected-(*1-TNOW-Pad15)") (class "Default")
      (node (ref "*1") (pin "15") (pinfunction "TNOW_15") (pintype "input+no_connect"))
    )
    (net (code "63") (name "unconnected-(K3-PadNC)") (class "Default")
      (node (ref "K3") (pin "NC") (pinfunction "NC_NC") (pintype "passive"))
    )
    (net (code "64") (name "unconnected-(K4-PadNC)") (class "Default")
      (node (ref "K4") (pin "NC") (pinfunction "NC_NC") (pintype "passive"))
    )
    (net (code "65") (name "unconnected-(MD1-NC-Pad32)") (class "Default")
      (node (ref "MD1") (pin "32") (pinfunction "NC_32") (pintype "passive+no_connect"))
    )
    (net (code "66") (name "unconnected-(U1-NC-Pad4)") (class "Default")
      (node (ref "U1") (pin "4") (pinfunction "NC_4") (pintype "passive+no_connect"))
    )
    (net (code "67") (name "unconnected-(U2-DOUT-Pad2)") (class "Default")
      (node (ref "U2") (pin "2") (pinfunction "DOUT_2") (pintype "output"))
    )
    (net (code "68") (name "unconnected-(USB-C1-SBU1-PadA8)") (class "Default")
      (node (ref "USB-C1") (pin "A8") (pinfunction "SBU1_A8") (pintype "power_in+no_connect"))
    )
    (net (code "69") (name "unconnected-(USB-C1-SBU2-PadB8)") (class "Default")
      (node (ref "USB-C1") (pin "B8") (pinfunction "SBU2_B8") (pintype "power_in+no_connect"))
    )
  )
)
